# lixie_digit_maxi.net
KiCad netlist of a schematic drawn in EAGLE
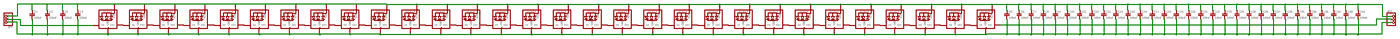
[diagram p0: schematic, sheet 1, overview]
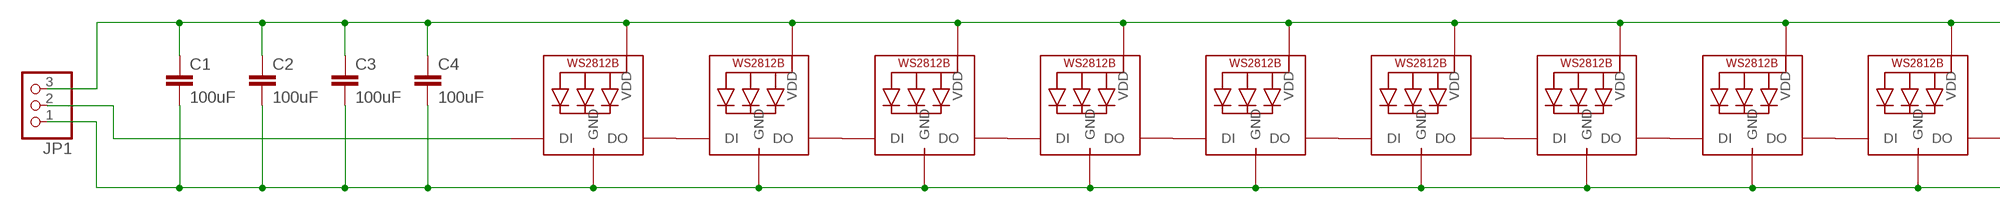
[diagram p1: schematic, sheet 1, part 1 of 4]
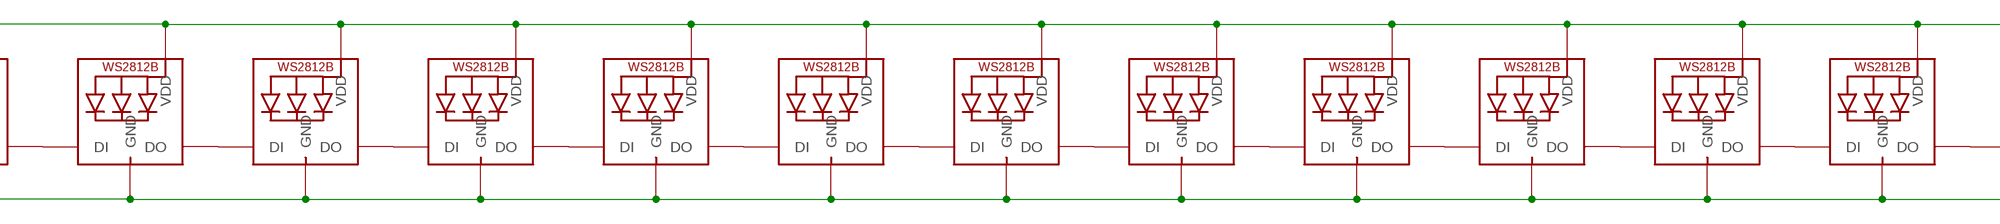
[diagram p2: schematic, sheet 1, part 2 of 4]
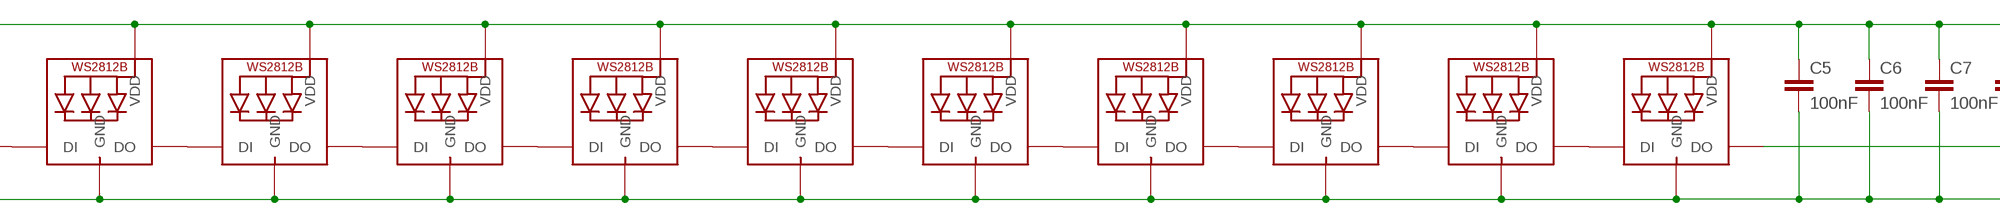
[diagram p3: schematic, sheet 1, part 3 of 4]
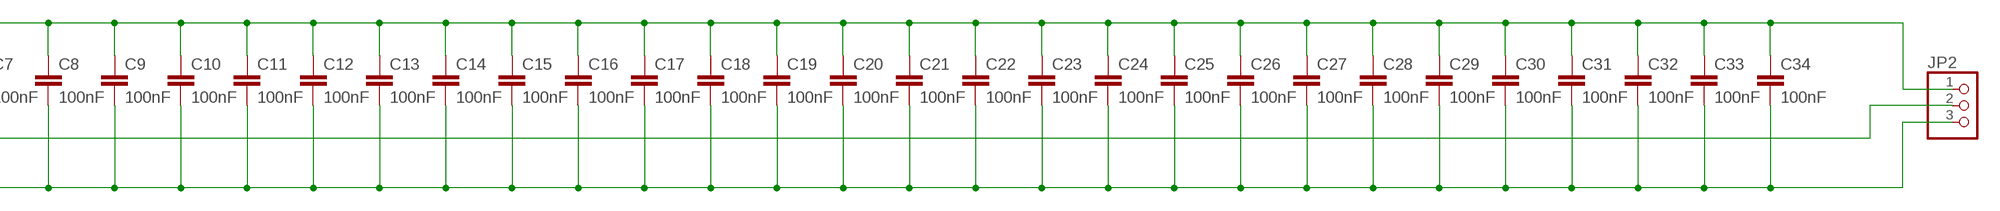
[diagram p4: schematic, sheet 1, part 4 of 4]

(export (version "E")
  (design (tool "Eeschema 10.0.6"))
  (components
    (comp (ref "C1")
      (value "100uF")
      (footprint "eagle-import:C1206K")
      (libsource (lib "eagle-import") (part "C-EUC1206K"))
    )
    (comp (ref "C2")
      (value "100uF")
      (footprint "eagle-import:C1206K")
      (libsource (lib "eagle-import") (part "C-EUC1206K"))
    )
    (comp (ref "C3")
      (value "100uF")
      (footprint "eagle-import:C1206K")
      (libsource (lib "eagle-import") (part "C-EUC1206K"))
    )
    (comp (ref "C4")
      (value "100uF")
      (footprint "eagle-import:C1206K")
      (libsource (lib "eagle-import") (part "C-EUC1206K"))
    )
    (comp (ref "C5")
      (value "100nF")
      (footprint "eagle-import:C0402K")
      (libsource (lib "eagle-import") (part "C-EUC0402K"))
    )
    (comp (ref "C6")
      (value "100nF")
      (footprint "eagle-import:C0402K")
      (libsource (lib "eagle-import") (part "C-EUC0402K"))
    )
    (comp (ref "C7")
      (value "100nF")
      (footprint "eagle-import:C0402K")
      (libsource (lib "eagle-import") (part "C-EUC0402K"))
    )
    (comp (ref "C8")
      (value "100nF")
      (footprint "eagle-import:C0402K")
      (libsource (lib "eagle-import") (part "C-EUC0402K"))
    )
    (comp (ref "C9")
      (value "100nF")
      (footprint "eagle-import:C0402K")
      (libsource (lib "eagle-import") (part "C-EUC0402K"))
    )
    (comp (ref "C10")
      (value "100nF")
      (footprint "eagle-import:C0402K")
      (libsource (lib "eagle-import") (part "C-EUC0402K"))
    )
    (comp (ref "C11")
      (value "100nF")
      (footprint "eagle-import:C0402K")
      (libsource (lib "eagle-import") (part "C-EUC0402K"))
    )
    (comp (ref "C12")
      (value "100nF")
      (footprint "eagle-import:C0402K")
      (libsource (lib "eagle-import") (part "C-EUC0402K"))
    )
    (comp (ref "C13")
      (value "100nF")
      (footprint "eagle-import:C0402K")
      (libsource (lib "eagle-import") (part "C-EUC0402K"))
    )
    (comp (ref "C14")
      (value "100nF")
      (footprint "eagle-import:C0402K")
      (libsource (lib "eagle-import") (part "C-EUC0402K"))
    )
    (comp (ref "C15")
      (value "100nF")
      (footprint "eagle-import:C0402K")
      (libsource (lib "eagle-import") (part "C-EUC0402K"))
    )
    (comp (ref "C16")
      (value "100nF")
      (footprint "eagle-import:C0402K")
      (libsource (lib "eagle-import") (part "C-EUC0402K"))
    )
    (comp (ref "C17")
      (value "100nF")
      (footprint "eagle-import:C0402K")
      (libsource (lib "eagle-import") (part "C-EUC0402K"))
    )
    (comp (ref "C18")
      (value "100nF")
      (footprint "eagle-import:C0402K")
      (libsource (lib "eagle-import") (part "C-EUC0402K"))
    )
    (comp (ref "C19")
      (value "100nF")
      (footprint "eagle-import:C0402K")
      (libsource (lib "eagle-import") (part "C-EUC0402K"))
    )
    (comp (ref "C20")
      (value "100nF")
      (footprint "eagle-import:C0402K")
      (libsource (lib "eagle-import") (part "C-EUC0402K"))
    )
    (comp (ref "C21")
      (value "100nF")
      (footprint "eagle-import:C0402K")
      (libsource (lib "eagle-import") (part "C-EUC0402K"))
    )
    (comp (ref "C22")
      (value "100nF")
      (footprint "eagle-import:C0402K")
      (libsource (lib "eagle-import") (part "C-EUC0402K"))
    )
    (comp (ref "C23")
      (value "100nF")
      (footprint "eagle-import:C0402K")
      (libsource (lib "eagle-import") (part "C-EUC0402K"))
    )
    (comp (ref "C24")
      (value "100nF")
      (footprint "eagle-import:C0402K")
      (libsource (lib "eagle-import") (part "C-EUC0402K"))
    )
    (comp (ref "C25")
      (value "100nF")
      (footprint "eagle-import:C0402K")
      (libsource (lib "eagle-import") (part "C-EUC0402K"))
    )
    (comp (ref "C26")
      (value "100nF")
      (footprint "eagle-import:C0402K")
      (libsource (lib "eagle-import") (part "C-EUC0402K"))
    )
    (comp (ref "C27")
      (value "100nF")
      (footprint "eagle-import:C0402K")
      (libsource (lib "eagle-import") (part "C-EUC0402K"))
    )
    (comp (ref "C28")
      (value "100nF")
      (footprint "eagle-import:C0402K")
      (libsource (lib "eagle-import") (part "C-EUC0402K"))
    )
    (comp (ref "C29")
      (value "100nF")
      (footprint "eagle-import:C0402K")
      (libsource (lib "eagle-import") (part "C-EUC0402K"))
    )
    (comp (ref "C30")
      (value "100nF")
      (footprint "eagle-import:C0402K")
      (libsource (lib "eagle-import") (part "C-EUC0402K"))
    )
    (comp (ref "C31")
      (value "100nF")
      (footprint "eagle-import:C0402K")
      (libsource (lib "eagle-import") (part "C-EUC0402K"))
    )
    (comp (ref "C32")
      (value "100nF")
      (footprint "eagle-import:C0402K")
      (libsource (lib "eagle-import") (part "C-EUC0402K"))
    )
    (comp (ref "C33")
      (value "100nF")
      (footprint "eagle-import:C0402K")
      (libsource (lib "eagle-import") (part "C-EUC0402K"))
    )
    (comp (ref "C34")
      (value "100nF")
      (footprint "eagle-import:C0402K")
      (libsource (lib "eagle-import") (part "C-EUC0402K"))
    )
    (comp (ref "JP1")
      (value "PINHD-1X3")
      (footprint "eagle-import:1X03")
      (libsource (lib "eagle-import") (part "PINHD-1X3"))
    )
    (comp (ref "JP2")
      (value "PINHD-1X3")
      (footprint "eagle-import:1X03")
      (libsource (lib "eagle-import") (part "PINHD-1X3"))
    )
    (comp (ref "LED1")
      (value "WS2812B5050")
      (footprint "eagle-import:WS2812B")
      (libsource (lib "eagle-import") (part "WS2812B5050"))
    )
    (comp (ref "LED2")
      (value "WS2812B5050")
      (footprint "eagle-import:WS2812B")
      (libsource (lib "eagle-import") (part "WS2812B5050"))
    )
    (comp (ref "LED3")
      (value "WS2812B5050")
      (footprint "eagle-import:WS2812B")
      (libsource (lib "eagle-import") (part "WS2812B5050"))
    )
    (comp (ref "LED4")
      (value "WS2812B5050")
      (footprint "eagle-import:WS2812B")
      (libsource (lib "eagle-import") (part "WS2812B5050"))
    )
    (comp (ref "LED5")
      (value "WS2812B5050")
      (footprint "eagle-import:WS2812B")
      (libsource (lib "eagle-import") (part "WS2812B5050"))
    )
    (comp (ref "LED6")
      (value "WS2812B5050")
      (footprint "eagle-import:WS2812B")
      (libsource (lib "eagle-import") (part "WS2812B5050"))
    )
    (comp (ref "LED7")
      (value "WS2812B5050")
      (footprint "eagle-import:WS2812B")
      (libsource (lib "eagle-import") (part "WS2812B5050"))
    )
    (comp (ref "LED8")
      (value "WS2812B5050")
      (footprint "eagle-import:WS2812B")
      (libsource (lib "eagle-import") (part "WS2812B5050"))
    )
    (comp (ref "LED9")
      (value "WS2812B5050")
      (footprint "eagle-import:WS2812B")
      (libsource (lib "eagle-import") (part "WS2812B5050"))
    )
    (comp (ref "LED10")
      (value "WS2812B5050")
      (footprint "eagle-import:WS2812B")
      (libsource (lib "eagle-import") (part "WS2812B5050"))
    )
    (comp (ref "LED11")
      (value "WS2812B5050")
      (footprint "eagle-import:WS2812B")
      (libsource (lib "eagle-import") (part "WS2812B5050"))
    )
    (comp (ref "LED12")
      (value "WS2812B5050")
      (footprint "eagle-import:WS2812B")
      (libsource (lib "eagle-import") (part "WS2812B5050"))
    )
    (comp (ref "LED13")
      (value "WS2812B5050")
      (footprint "eagle-import:WS2812B")
      (libsource (lib "eagle-import") (part "WS2812B5050"))
    )
    (comp (ref "LED14")
      (value "WS2812B5050")
      (footprint "eagle-import:WS2812B")
      (libsource (lib "eagle-import") (part "WS2812B5050"))
    )
    (comp (ref "LED15")
      (value "WS2812B5050")
      (footprint "eagle-import:WS2812B")
      (libsource (lib "eagle-import") (part "WS2812B5050"))
    )
    (comp (ref "LED16")
      (value "WS2812B5050")
      (footprint "eagle-import:WS2812B")
      (libsource (lib "eagle-import") (part "WS2812B5050"))
    )
    (comp (ref "LED17")
      (value "WS2812B5050")
      (footprint "eagle-import:WS2812B")
      (libsource (lib "eagle-import") (part "WS2812B5050"))
    )
    (comp (ref "LED18")
      (value "WS2812B5050")
      (footprint "eagle-import:WS2812B")
      (libsource (lib "eagle-import") (part "WS2812B5050"))
    )
    (comp (ref "LED19")
      (value "WS2812B5050")
      (footprint "eagle-import:WS2812B")
      (libsource (lib "eagle-import") (part "WS2812B5050"))
    )
    (comp (ref "LED20")
      (value "WS2812B5050")
      (footprint "eagle-import:WS2812B")
      (libsource (lib "eagle-import") (part "WS2812B5050"))
    )
    (comp (ref "LED21")
      (value "WS2812B5050")
      (footprint "eagle-import:WS2812B")
      (libsource (lib "eagle-import") (part "WS2812B5050"))
    )
    (comp (ref "LED22")
      (value "WS2812B5050")
      (footprint "eagle-import:WS2812B")
      (libsource (lib "eagle-import") (part "WS2812B5050"))
    )
    (comp (ref "LED23")
      (value "WS2812B5050")
      (footprint "eagle-import:WS2812B")
      (libsource (lib "eagle-import") (part "WS2812B5050"))
    )
    (comp (ref "LED24")
      (value "WS2812B5050")
      (footprint "eagle-import:WS2812B")
      (libsource (lib "eagle-import") (part "WS2812B5050"))
    )
    (comp (ref "LED25")
      (value "WS2812B5050")
      (footprint "eagle-import:WS2812B")
      (libsource (lib "eagle-import") (part "WS2812B5050"))
    )
    (comp (ref "LED26")
      (value "WS2812B5050")
      (footprint "eagle-import:WS2812B")
      (libsource (lib "eagle-import") (part "WS2812B5050"))
    )
    (comp (ref "LED27")
      (value "WS2812B5050")
      (footprint "eagle-import:WS2812B")
      (libsource (lib "eagle-import") (part "WS2812B5050"))
    )
    (comp (ref "LED28")
      (value "WS2812B5050")
      (footprint "eagle-import:WS2812B")
      (libsource (lib "eagle-import") (part "WS2812B5050"))
    )
    (comp (ref "LED29")
      (value "WS2812B5050")
      (footprint "eagle-import:WS2812B")
      (libsource (lib "eagle-import") (part "WS2812B5050"))
    )
    (comp (ref "LED30")
      (value "WS2812B5050")
      (footprint "eagle-import:WS2812B")
      (libsource (lib "eagle-import") (part "WS2812B5050"))
    )
  )
  (nets
    (net (code "1") (name "Net-(LED1-DI)") (class "Default")
      (node (ref "JP1") (pin "2") (pinfunction "2_2") (pintype "passive"))
      (node (ref "LED1") (pin "4-DIN") (pinfunction "DI_4-DIN") (pintype "input"))
    )
    (net (code "2") (name "Net-(LED1-DO)") (class "Default")
      (node (ref "LED1") (pin "2-DOUT") (pinfunction "DO_2-DOUT") (pintype "output"))
      (node (ref "LED2") (pin "4-DIN") (pinfunction "DI_4-DIN") (pintype "input"))
    )
    (net (code "3") (name "Net-(LED1-GND)") (class "Default")
      (node (ref "C1") (pin "2") (pinfunction "2_2") (pintype "passive"))
      (node (ref "C10") (pin "2") (pinfunction "2_2") (pintype "passive"))
      (node (ref "C11") (pin "2") (pinfunction "2_2") (pintype "passive"))
      (node (ref "C12") (pin "2") (pinfunction "2_2") (pintype "passive"))
      (node (ref "C13") (pin "2") (pinfunction "2_2") (pintype "passive"))
      (node (ref "C14") (pin "2") (pinfunction "2_2") (pintype "passive"))
      (node (ref "C15") (pin "2") (pinfunction "2_2") (pintype "passive"))
      (node (ref "C16") (pin "2") (pinfunction "2_2") (pintype "passive"))
      (node (ref "C17") (pin "2") (pinfunction "2_2") (pintype "passive"))
      (node (ref "C18") (pin "2") (pinfunction "2_2") (pintype "passive"))
      (node (ref "C19") (pin "2") (pinfunction "2_2") (pintype "passive"))
      (node (ref "C2") (pin "2") (pinfunction "2_2") (pintype "passive"))
      (node (ref "C20") (pin "2") (pinfunction "2_2") (pintype "passive"))
      (node (ref "C21") (pin "2") (pinfunction "2_2") (pintype "passive"))
      (node (ref "C22") (pin "2") (pinfunction "2_2") (pintype "passive"))
      (node (ref "C23") (pin "2") (pinfunction "2_2") (pintype "passive"))
      (node (ref "C24") (pin "2") (pinfunction "2_2") (pintype "passive"))
      (node (ref "C25") (pin "2") (pinfunction "2_2") (pintype "passive"))
      (node (ref "C26") (pin "2") (pinfunction "2_2") (pintype "passive"))
      (node (ref "C27") (pin "2") (pinfunction "2_2") (pintype "passive"))
      (node (ref "C28") (pin "2") (pinfunction "2_2") (pintype "passive"))
      (node (ref "C29") (pin "2") (pinfunction "2_2") (pintype "passive"))
      (node (ref "C3") (pin "2") (pinfunction "2_2") (pintype "passive"))
      (node (ref "C30") (pin "2") (pinfunction "2_2") (pintype "passive"))
      (node (ref "C31") (pin "2") (pinfunction "2_2") (pintype "passive"))
      (node (ref "C32") (pin "2") (pinfunction "2_2") (pintype "passive"))
      (node (ref "C33") (pin "2") (pinfunction "2_2") (pintype "passive"))
      (node (ref "C34") (pin "2") (pinfunction "2_2") (pintype "passive"))
      (node (ref "C4") (pin "2") (pinfunction "2_2") (pintype "passive"))
      (node (ref "C5") (pin "2") (pinfunction "2_2") (pintype "passive"))
      (node (ref "C6") (pin "2") (pinfunction "2_2") (pintype "passive"))
      (node (ref "C7") (pin "2") (pinfunction "2_2") (pintype "passive"))
      (node (ref "C8") (pin "2") (pinfunction "2_2") (pintype "passive"))
      (node (ref "C9") (pin "2") (pinfunction "2_2") (pintype "passive"))
      (node (ref "JP1") (pin "1") (pinfunction "1_1") (pintype "passive"))
      (node (ref "JP2") (pin "3") (pinfunction "3_3") (pintype "passive"))
      (node (ref "LED1") (pin "3-GND") (pinfunction "GND_3-GND") (pintype "power_in"))
      (node (ref "LED10") (pin "3-GND") (pinfunction "GND_3-GND") (pintype "power_in"))
      (node (ref "LED11") (pin "3-GND") (pinfunction "GND_3-GND") (pintype "power_in"))
      (node (ref "LED12") (pin "3-GND") (pinfunction "GND_3-GND") (pintype "power_in"))
      (node (ref "LED13") (pin "3-GND") (pinfunction "GND_3-GND") (pintype "power_in"))
      (node (ref "LED14") (pin "3-GND") (pinfunction "GND_3-GND") (pintype "power_in"))
      (node (ref "LED15") (pin "3-GND") (pinfunction "GND_3-GND") (pintype "power_in"))
      (node (ref "LED16") (pin "3-GND") (pinfunction "GND_3-GND") (pintype "power_in"))
      (node (ref "LED17") (pin "3-GND") (pinfunction "GND_3-GND") (pintype "power_in"))
      (node (ref "LED18") (pin "3-GND") (pinfunction "GND_3-GND") (pintype "power_in"))
      (node (ref "LED19") (pin "3-GND") (pinfunction "GND_3-GND") (pintype "power_in"))
      (node (ref "LED2") (pin "3-GND") (pinfunction "GND_3-GND") (pintype "power_in"))
      (node (ref "LED20") (pin "3-GND") (pinfunction "GND_3-GND") (pintype "power_in"))
      (node (ref "LED21") (pin "3-GND") (pinfunction "GND_3-GND") (pintype "power_in"))
      (node (ref "LED22") (pin "3-GND") (pinfunction "GND_3-GND") (pintype "power_in"))
      (node (ref "LED23") (pin "3-GND") (pinfunction "GND_3-GND") (pintype "power_in"))
      (node (ref "LED24") (pin "3-GND") (pinfunction "GND_3-GND") (pintype "power_in"))
      (node (ref "LED25") (pin "3-GND") (pinfunction "GND_3-GND") (pintype "power_in"))
      (node (ref "LED26") (pin "3-GND") (pinfunction "GND_3-GND") (pintype "power_in"))
      (node (ref "LED27") (pin "3-GND") (pinfunction "GND_3-GND") (pintype "power_in"))
      (node (ref "LED28") (pin "3-GND") (pinfunction "GND_3-GND") (pintype "power_in"))
      (node (ref "LED29") (pin "3-GND") (pinfunction "GND_3-GND") (pintype "power_in"))
      (node (ref "LED3") (pin "3-GND") (pinfunction "GND_3-GND") (pintype "power_in"))
      (node (ref "LED30") (pin "3-GND") (pinfunction "GND_3-GND") (pintype "power_in"))
      (node (ref "LED4") (pin "3-GND") (pinfunction "GND_3-GND") (pintype "power_in"))
      (node (ref "LED5") (pin "3-GND") (pinfunction "GND_3-GND") (pintype "power_in"))
      (node (ref "LED6") (pin "3-GND") (pinfunction "GND_3-GND") (pintype "power_in"))
      (node (ref "LED7") (pin "3-GND") (pinfunction "GND_3-GND") (pintype "power_in"))
      (node (ref "LED8") (pin "3-GND") (pinfunction "GND_3-GND") (pintype "power_in"))
      (node (ref "LED9") (pin "3-GND") (pinfunction "GND_3-GND") (pintype "power_in"))
    )
    (net (code "4") (name "Net-(LED1-VDD)") (class "Default")
      (node (ref "C1") (pin "1") (pinfunction "1_1") (pintype "passive"))
      (node (ref "C10") (pin "1") (pinfunction "1_1") (pintype "passive"))
      (node (ref "C11") (pin "1") (pinfunction "1_1") (pintype "passive"))
      (node (ref "C12") (pin "1") (pinfunction "1_1") (pintype "passive"))
      (node (ref "C13") (pin "1") (pinfunction "1_1") (pintype "passive"))
      (node (ref "C14") (pin "1") (pinfunction "1_1") (pintype "passive"))
      (node (ref "C15") (pin "1") (pinfunction "1_1") (pintype "passive"))
      (node (ref "C16") (pin "1") (pinfunction "1_1") (pintype "passive"))
      (node (ref "C17") (pin "1") (pinfunction "1_1") (pintype "passive"))
      (node (ref "C18") (pin "1") (pinfunction "1_1") (pintype "passive"))
      (node (ref "C19") (pin "1") (pinfunction "1_1") (pintype "passive"))
      (node (ref "C2") (pin "1") (pinfunction "1_1") (pintype "passive"))
      (node (ref "C20") (pin "1") (pinfunction "1_1") (pintype "passive"))
      (node (ref "C21") (pin "1") (pinfunction "1_1") (pintype "passive"))
      (node (ref "C22") (pin "1") (pinfunction "1_1") (pintype "passive"))
      (node (ref "C23") (pin "1") (pinfunction "1_1") (pintype "passive"))
      (node (ref "C24") (pin "1") (pinfunction "1_1") (pintype "passive"))
      (node (ref "C25") (pin "1") (pinfunction "1_1") (pintype "passive"))
      (node (ref "C26") (pin "1") (pinfunction "1_1") (pintype "passive"))
      (node (ref "C27") (pin "1") (pinfunction "1_1") (pintype "passive"))
      (node (ref "C28") (pin "1") (pinfunction "1_1") (pintype "passive"))
      (node (ref "C29") (pin "1") (pinfunction "1_1") (pintype "passive"))
      (node (ref "C3") (pin "1") (pinfunction "1_1") (pintype "passive"))
      (node (ref "C30") (pin "1") (pinfunction "1_1") (pintype "passive"))
      (node (ref "C31") (pin "1") (pinfunction "1_1") (pintype "passive"))
      (node (ref "C32") (pin "1") (pinfunction "1_1") (pintype "passive"))
      (node (ref "C33") (pin "1") (pinfunction "1_1") (pintype "passive"))
      (node (ref "C34") (pin "1") (pinfunction "1_1") (pintype "passive"))
      (node (ref "C4") (pin "1") (pinfunction "1_1") (pintype "passive"))
      (node (ref "C5") (pin "1") (pinfunction "1_1") (pintype "passive"))
      (node (ref "C6") (pin "1") (pinfunction "1_1") (pintype "passive"))
      (node (ref "C7") (pin "1") (pinfunction "1_1") (pintype "passive"))
      (node (ref "C8") (pin "1") (pinfunction "1_1") (pintype "passive"))
      (node (ref "C9") (pin "1") (pinfunction "1_1") (pintype "passive"))
      (node (ref "JP1") (pin "3") (pinfunction "3_3") (pintype "passive"))
      (node (ref "JP2") (pin "1") (pinfunction "1_1") (pintype "passive"))
      (node (ref "LED1") (pin "1-VDD") (pinfunction "VDD_1-VDD") (pintype "power_in"))
      (node (ref "LED10") (pin "1-VDD") (pinfunction "VDD_1-VDD") (pintype "power_in"))
      (node (ref "LED11") (pin "1-VDD") (pinfunction "VDD_1-VDD") (pintype "power_in"))
      (node (ref "LED12") (pin "1-VDD") (pinfunction "VDD_1-VDD") (pintype "power_in"))
      (node (ref "LED13") (pin "1-VDD") (pinfunction "VDD_1-VDD") (pintype "power_in"))
      (node (ref "LED14") (pin "1-VDD") (pinfunction "VDD_1-VDD") (pintype "power_in"))
      (node (ref "LED15") (pin "1-VDD") (pinfunction "VDD_1-VDD") (pintype "power_in"))
      (node (ref "LED16") (pin "1-VDD") (pinfunction "VDD_1-VDD") (pintype "power_in"))
      (node (ref "LED17") (pin "1-VDD") (pinfunction "VDD_1-VDD") (pintype "power_in"))
      (node (ref "LED18") (pin "1-VDD") (pinfunction "VDD_1-VDD") (pintype "power_in"))
      (node (ref "LED19") (pin "1-VDD") (pinfunction "VDD_1-VDD") (pintype "power_in"))
      (node (ref "LED2") (pin "1-VDD") (pinfunction "VDD_1-VDD") (pintype "power_in"))
      (node (ref "LED20") (pin "1-VDD") (pinfunction "VDD_1-VDD") (pintype "power_in"))
      (node (ref "LED21") (pin "1-VDD") (pinfunction "VDD_1-VDD") (pintype "power_in"))
      (node (ref "LED22") (pin "1-VDD") (pinfunction "VDD_1-VDD") (pintype "power_in"))
      (node (ref "LED23") (pin "1-VDD") (pinfunction "VDD_1-VDD") (pintype "power_in"))
      (node (ref "LED24") (pin "1-VDD") (pinfunction "VDD_1-VDD") (pintype "power_in"))
      (node (ref "LED25") (pin "1-VDD") (pinfunction "VDD_1-VDD") (pintype "power_in"))
      (node (ref "LED26") (pin "1-VDD") (pinfunction "VDD_1-VDD") (pintype "power_in"))
      (node (ref "LED27") (pin "1-VDD") (pinfunction "VDD_1-VDD") (pintype "power_in"))
      (node (ref "LED28") (pin "1-VDD") (pinfunction "VDD_1-VDD") (pintype "power_in"))
      (node (ref "LED29") (pin "1-VDD") (pinfunction "VDD_1-VDD") (pintype "power_in"))
      (node (ref "LED3") (pin "1-VDD") (pinfunction "VDD_1-VDD") (pintype "power_in"))
      (node (ref "LED30") (pin "1-VDD") (pinfunction "VDD_1-VDD") (pintype "power_in"))
      (node (ref "LED4") (pin "1-VDD") (pinfunction "VDD_1-VDD") (pintype "power_in"))
      (node (ref "LED5") (pin "1-VDD") (pinfunction "VDD_1-VDD") (pintype "power_in"))
      (node (ref "LED6") (pin "1-VDD") (pinfunction "VDD_1-VDD") (pintype "power_in"))
      (node (ref "LED7") (pin "1-VDD") (pinfunction "VDD_1-VDD") (pintype "power_in"))
      (node (ref "LED8") (pin "1-VDD") (pinfunction "VDD_1-VDD") (pintype "power_in"))
      (node (ref "LED9") (pin "1-VDD") (pinfunction "VDD_1-VDD") (pintype "power_in"))
    )
    (net (code "5") (name "Net-(LED2-DO)") (class "Default")
      (node (ref "LED2") (pin "2-DOUT") (pinfunction "DO_2-DOUT") (pintype "output"))
      (node (ref "LED3") (pin "4-DIN") (pinfunction "DI_4-DIN") (pintype "input"))
    )
    (net (code "6") (name "Net-(LED3-DO)") (class "Default")
      (node (ref "LED3") (pin "2-DOUT") (pinfunction "DO_2-DOUT") (pintype "output"))
      (node (ref "LED4") (pin "4-DIN") (pinfunction "DI_4-DIN") (pintype "input"))
    )
    (net (code "7") (name "Net-(LED4-DO)") (class "Default")
      (node (ref "LED4") (pin "2-DOUT") (pinfunction "DO_2-DOUT") (pintype "output"))
      (node (ref "LED5") (pin "4-DIN") (pinfunction "DI_4-DIN") (pintype "input"))
    )
    (net (code "8") (name "Net-(LED5-DO)") (class "Default")
      (node (ref "LED5") (pin "2-DOUT") (pinfunction "DO_2-DOUT") (pintype "output"))
      (node (ref "LED6") (pin "4-DIN") (pinfunction "DI_4-DIN") (pintype "input"))
    )
    (net (code "9") (name "Net-(LED6-DO)") (class "Default")
      (node (ref "LED6") (pin "2-DOUT") (pinfunction "DO_2-DOUT") (pintype "output"))
      (node (ref "LED7") (pin "4-DIN") (pinfunction "DI_4-DIN") (pintype "input"))
    )
    (net (code "10") (name "Net-(LED7-DO)") (class "Default")
      (node (ref "LED7") (pin "2-DOUT") (pinfunction "DO_2-DOUT") (pintype "output"))
      (node (ref "LED8") (pin "4-DIN") (pinfunction "DI_4-DIN") (pintype "input"))
    )
    (net (code "11") (name "Net-(LED8-DO)") (class "Default")
      (node (ref "LED8") (pin "2-DOUT") (pinfunction "DO_2-DOUT") (pintype "output"))
      (node (ref "LED9") (pin "4-DIN") (pinfunction "DI_4-DIN") (pintype "input"))
    )
    (net (code "12") (name "Net-(LED10-DI)") (class "Default")
      (node (ref "LED10") (pin "4-DIN") (pinfunction "DI_4-DIN") (pintype "input"))
      (node (ref "LED9") (pin "2-DOUT") (pinfunction "DO_2-DOUT") (pintype "output"))
    )
    (net (code "13") (name "Net-(LED10-DO)") (class "Default")
      (node (ref "LED10") (pin "2-DOUT") (pinfunction "DO_2-DOUT") (pintype "output"))
      (node (ref "LED11") (pin "4-DIN") (pinfunction "DI_4-DIN") (pintype "input"))
    )
    (net (code "14") (name "Net-(LED11-DO)") (class "Default")
      (node (ref "LED11") (pin "2-DOUT") (pinfunction "DO_2-DOUT") (pintype "output"))
      (node (ref "LED12") (pin "4-DIN") (pinfunction "DI_4-DIN") (pintype "input"))
    )
    (net (code "15") (name "Net-(LED12-DO)") (class "Default")
      (node (ref "LED12") (pin "2-DOUT") (pinfunction "DO_2-DOUT") (pintype "output"))
      (node (ref "LED13") (pin "4-DIN") (pinfunction "DI_4-DIN") (pintype "input"))
    )
    (net (code "16") (name "Net-(LED13-DO)") (class "Default")
      (node (ref "LED13") (pin "2-DOUT") (pinfunction "DO_2-DOUT") (pintype "output"))
      (node (ref "LED14") (pin "4-DIN") (pinfunction "DI_4-DIN") (pintype "input"))
    )
    (net (code "17") (name "Net-(LED14-DO)") (class "Default")
      (node (ref "LED14") (pin "2-DOUT") (pinfunction "DO_2-DOUT") (pintype "output"))
      (node (ref "LED15") (pin "4-DIN") (pinfunction "DI_4-DIN") (pintype "input"))
    )
    (net (code "18") (name "Net-(LED15-DO)") (class "Default")
      (node (ref "LED15") (pin "2-DOUT") (pinfunction "DO_2-DOUT") (pintype "output"))
      (node (ref "LED16") (pin "4-DIN") (pinfunction "DI_4-DIN") (pintype "input"))
    )
    (net (code "19") (name "Net-(LED16-DO)") (class "Default")
      (node (ref "LED16") (pin "2-DOUT") (pinfunction "DO_2-DOUT") (pintype "output"))
      (node (ref "LED17") (pin "4-DIN") (pinfunction "DI_4-DIN") (pintype "input"))
    )
    (net (code "20") (name "Net-(LED17-DO)") (class "Default")
      (node (ref "LED17") (pin "2-DOUT") (pinfunction "DO_2-DOUT") (pintype "output"))
      (node (ref "LED18") (pin "4-DIN") (pinfunction "DI_4-DIN") (pintype "input"))
    )
    (net (code "21") (name "Net-(LED18-DO)") (class "Default")
      (node (ref "LED18") (pin "2-DOUT") (pinfunction "DO_2-DOUT") (pintype "output"))
      (node (ref "LED19") (pin "4-DIN") (pinfunction "DI_4-DIN") (pintype "input"))
    )
    (net (code "22") (name "Net-(LED19-DO)") (class "Default")
      (node (ref "LED19") (pin "2-DOUT") (pinfunction "DO_2-DOUT") (pintype "output"))
      (node (ref "LED20") (pin "4-DIN") (pinfunction "DI_4-DIN") (pintype "input"))
    )
    (net (code "23") (name "Net-(LED20-DO)") (class "Default")
      (node (ref "LED20") (pin "2-DOUT") (pinfunction "DO_2-DOUT") (pintype "output"))
      (node (ref "LED21") (pin "4-DIN") (pinfunction "DI_4-DIN") (pintype "input"))
    )
    (net (code "24") (name "Net-(LED21-DO)") (class "Default")
      (node (ref "LED21") (pin "2-DOUT") (pinfunction "DO_2-DOUT") (pintype "output"))
      (node (ref "LED22") (pin "4-DIN") (pinfunction "DI_4-DIN") (pintype "input"))
    )
    (net (code "25") (name "Net-(LED22-DO)") (class "Default")
      (node (ref "LED22") (pin "2-DOUT") (pinfunction "DO_2-DOUT") (pintype "output"))
      (node (ref "LED23") (pin "4-DIN") (pinfunction "DI_4-DIN") (pintype "input"))
    )
    (net (code "26") (name "Net-(LED23-DO)") (class "Default")
      (node (ref "LED23") (pin "2-DOUT") (pinfunction "DO_2-DOUT") (pintype "output"))
      (node (ref "LED24") (pin "4-DIN") (pinfunction "DI_4-DIN") (pintype "input"))
    )
    (net (code "27") (name "Net-(LED24-DO)") (class "Default")
      (node (ref "LED24") (pin "2-DOUT") (pinfunction "DO_2-DOUT") (pintype "output"))
      (node (ref "LED25") (pin "4-DIN") (pinfunction "DI_4-DIN") (pintype "input"))
    )
    (net (code "28") (name "Net-(LED25-DO)") (class "Default")
      (node (ref "LED25") (pin "2-DOUT") (pinfunction "DO_2-DOUT") (pintype "output"))
      (node (ref "LED26") (pin "4-DIN") (pinfunction "DI_4-DIN") (pintype "input"))
    )
    (net (code "29") (name "Net-(LED26-DO)") (class "Default")
      (node (ref "LED26") (pin "2-DOUT") (pinfunction "DO_2-DOUT") (pintype "output"))
      (node (ref "LED27") (pin "4-DIN") (pinfunction "DI_4-DIN") (pintype "input"))
    )
    (net (code "30") (name "Net-(LED27-DO)") (class "Default")
      (node (ref "LED27") (pin "2-DOUT") (pinfunction "DO_2-DOUT") (pintype "output"))
      (node (ref "LED28") (pin "4-DIN") (pinfunction "DI_4-DIN") (pintype "input"))
    )
    (net (code "31") (name "Net-(LED28-DO)") (class "Default")
      (node (ref "LED28") (pin "2-DOUT") (pinfunction "DO_2-DOUT") (pintype "output"))
      (node (ref "LED29") (pin "4-DIN") (pinfunction "DI_4-DIN") (pintype "input"))
    )
    (net (code "32") (name "Net-(LED29-DO)") (class "Default")
      (node (ref "LED29") (pin "2-DOUT") (pinfunction "DO_2-DOUT") (pintype "output"))
      (node (ref "LED30") (pin "4-DIN") (pinfunction "DI_4-DIN") (pintype "input"))
    )
    (net (code "33") (name "Net-(LED30-DO)") (class "Default")
      (node (ref "JP2") (pin "2") (pinfunction "2_2") (pintype "passive"))
      (node (ref "LED30") (pin "2-DOUT") (pinfunction "DO_2-DOUT") (pintype "output"))
    )
  )
)
